# SCH_arduino_timer_mertvyak_2023-02-15.net
KiCad netlist of a schematic drawn in EasyEDA
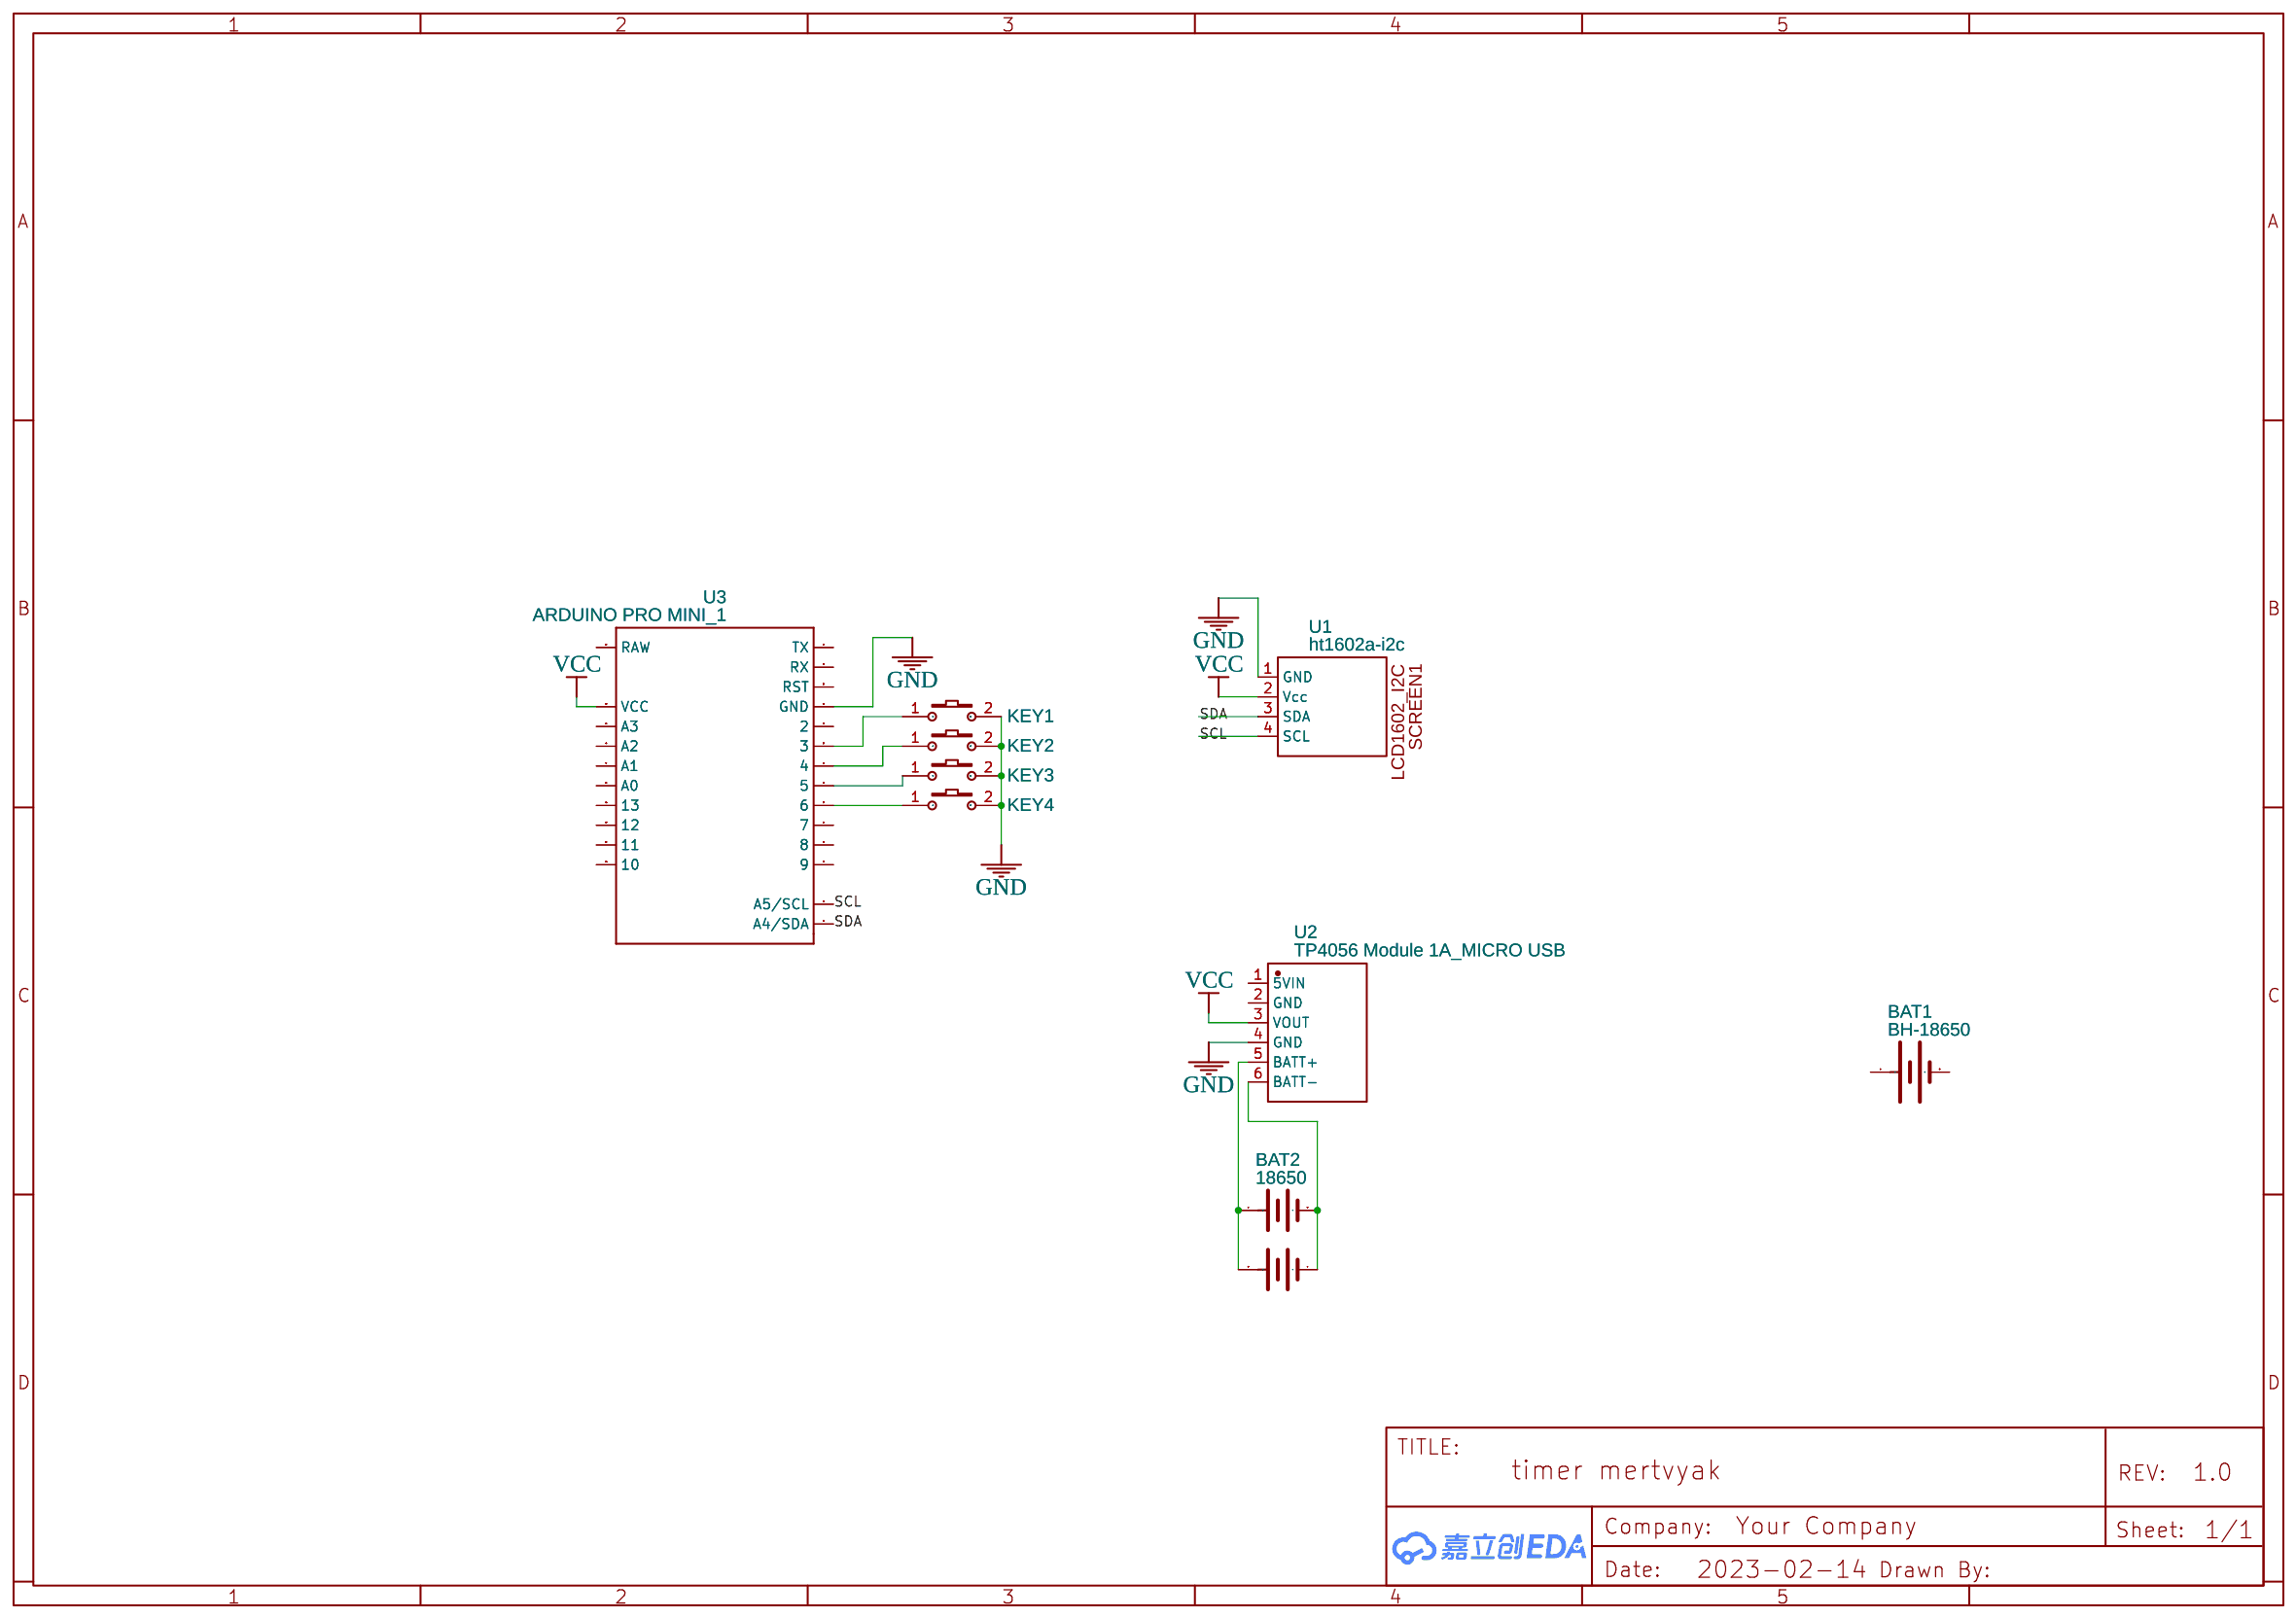
[diagram p0: schematic sheet]

(export (version "E")
  (design (tool "Eeschema 10.0.6"))
  (components
    (comp (ref "BAT1")
      (value "BH-18650")
      (fields (field (name "BOM_Supplier Part") "C9900017971"))
      (libsource (lib "") (part "BH-18650"))
    )
    (comp (ref "BAT2")
      (value "18650")
      (fields
        (field (name "BOM_Manufacturer Part") "18650并联电池盒")
        (field (name "BOM_Supplier Part") "C9900010344")
      )
      (libsource (lib "") (part "18650并联电池盒"))
    )
    (comp (ref "KEY1")
      (value "K2-3.6×6.1_SMD")
      (fields
        (field (name "BOM_Manufacturer Part") "K2-1107ST-A4SW-06")
        (field (name "BOM_Supplier Part") "C118141")
      )
      (libsource (lib "") (part "K2-3.6×6.1_SMD"))
    )
    (comp (ref "KEY2")
      (value "K2-3.6×6.1_SMD")
      (fields
        (field (name "BOM_Manufacturer Part") "K2-1107ST-A4SW-06")
        (field (name "BOM_Supplier Part") "C118141")
      )
      (libsource (lib "") (part "K2-3.6×6.1_SMD"))
    )
    (comp (ref "KEY3")
      (value "K2-3.6×6.1_SMD")
      (fields
        (field (name "BOM_Manufacturer Part") "K2-1107ST-A4SW-06")
        (field (name "BOM_Supplier Part") "C118141")
      )
      (libsource (lib "") (part "K2-3.6×6.1_SMD"))
    )
    (comp (ref "KEY4")
      (value "K2-3.6×6.1_SMD")
      (fields
        (field (name "BOM_Manufacturer Part") "K2-1107ST-A4SW-06")
        (field (name "BOM_Supplier Part") "C118141")
      )
      (libsource (lib "") (part "K2-3.6×6.1_SMD"))
    )
    (comp (ref "U1") (value "ht1602a-i2c") (libsource (lib "") (part "ht1602a-i2c")))
    (comp (ref "U2")
      (value "TP4056 Module 1A_MICRO USB")
      (fields
        (field (name "BOM_Manufacturer Part") "TP4056 MICROUSB 1A")
        (field (name "BOM_Supplier Part") "EC-1275")
      )
      (libsource (lib "") (part "TP4056 Module 1A_MICRO USB"))
    )
    (comp (ref "U3") (value "ARDUINO PRO MINI_1") (libsource (lib "") (part "ARDUINO PRO MINI_1")))
  )
  (nets
    (net (code "1") (name "/SCL") (class "Default")
      (node (ref "U1") (pin "4") (pinfunction "SCL_4") (pintype "unspecified"))
      (node (ref "U3") (pin "A5") (pinfunction "A5/SCL_A5") (pintype "unspecified"))
    )
    (net (code "2") (name "/SDA") (class "Default")
      (node (ref "U1") (pin "3") (pinfunction "SDA_3") (pintype "unspecified"))
      (node (ref "U3") (pin "A4") (pinfunction "A4/SDA_A4") (pintype "unspecified"))
    )
    (net (code "3") (name "GND") (class "Default")
      (node (ref "KEY1") (pin "2") (pinfunction "2_2") (pintype "unspecified"))
      (node (ref "KEY2") (pin "2") (pinfunction "2_2") (pintype "unspecified"))
      (node (ref "KEY3") (pin "2") (pinfunction "2_2") (pintype "unspecified"))
      (node (ref "KEY4") (pin "2") (pinfunction "2_2") (pintype "unspecified"))
      (node (ref "U1") (pin "1") (pinfunction "GND_1") (pintype "unspecified"))
      (node (ref "U2") (pin "4") (pinfunction "GND_4") (pintype "unspecified"))
      (node (ref "U3") (pin "GND") (pinfunction "GND_GND") (pintype "unspecified"))
    )
    (net (code "4") (name "Net-(U2-BATT+)") (class "Default")
      (node (ref "BAT2") (pin "1") (pinfunction "+_1") (pintype "passive"))
      (node (ref "BAT2") (pin "2") (pinfunction "+_2") (pintype "passive"))
      (node (ref "U2") (pin "5") (pinfunction "BATT+_5") (pintype "unspecified"))
    )
    (net (code "5") (name "Net-(U2-BATT-)") (class "Default")
      (node (ref "BAT2") (pin "3") (pinfunction "-_3") (pintype "passive"))
      (node (ref "BAT2") (pin "4") (pinfunction "-_4") (pintype "passive"))
      (node (ref "U2") (pin "6") (pinfunction "BATT-_6") (pintype "unspecified"))
    )
    (net (code "6") (name "Net-(U3-3)") (class "Default")
      (node (ref "KEY1") (pin "1") (pinfunction "1_1") (pintype "unspecified"))
      (node (ref "U3") (pin "D3") (pinfunction "3_D3") (pintype "unspecified"))
    )
    (net (code "7") (name "Net-(U3-4)") (class "Default")
      (node (ref "KEY2") (pin "1") (pinfunction "1_1") (pintype "unspecified"))
      (node (ref "U3") (pin "D4") (pinfunction "4_D4") (pintype "unspecified"))
    )
    (net (code "8") (name "Net-(U3-5)") (class "Default")
      (node (ref "KEY3") (pin "1") (pinfunction "1_1") (pintype "unspecified"))
      (node (ref "U3") (pin "D5") (pinfunction "5_D5") (pintype "unspecified"))
    )
    (net (code "9") (name "Net-(U3-6)") (class "Default")
      (node (ref "KEY4") (pin "1") (pinfunction "1_1") (pintype "unspecified"))
      (node (ref "U3") (pin "D6") (pinfunction "6_D6") (pintype "unspecified"))
    )
    (net (code "10") (name "VCC") (class "Default")
      (node (ref "U1") (pin "2") (pinfunction "Vcc_2") (pintype "unspecified"))
      (node (ref "U2") (pin "3") (pinfunction "VOUT_3") (pintype "unspecified"))
      (node (ref "U3") (pin "VCC") (pinfunction "VCC_VCC") (pintype "unspecified"))
    )
    (net (code "11") (name "unconnected-(BAT1-+-Pad2)") (class "Default")
      (node (ref "BAT1") (pin "2") (pinfunction "+_2") (pintype "passive"))
    )
    (net (code "12") (name "unconnected-(BAT1---Pad1)") (class "Default")
      (node (ref "BAT1") (pin "1") (pinfunction "-_1") (pintype "passive"))
    )
    (net (code "13") (name "unconnected-(U2-5VIN-Pad1)") (class "Default")
      (node (ref "U2") (pin "1") (pinfunction "5VIN_1") (pintype "unspecified"))
    )
    (net (code "14") (name "unconnected-(U2-GND-Pad2)") (class "Default")
      (node (ref "U2") (pin "2") (pinfunction "GND_2") (pintype "unspecified"))
    )
    (net (code "15") (name "unconnected-(U3-2-PadD2)") (class "Default")
      (node (ref "U3") (pin "D2") (pinfunction "2_D2") (pintype "unspecified"))
    )
    (net (code "16") (name "unconnected-(U3-7-PadD7)") (class "Default")
      (node (ref "U3") (pin "D7") (pinfunction "7_D7") (pintype "unspecified"))
    )
    (net (code "17") (name "unconnected-(U3-8-PadD8)") (class "Default")
      (node (ref "U3") (pin "D8") (pinfunction "8_D8") (pintype "unspecified"))
    )
    (net (code "18") (name "unconnected-(U3-9-PadD9)") (class "Default")
      (node (ref "U3") (pin "D9") (pinfunction "9_D9") (pintype "unspecified"))
    )
    (net (code "19") (name "unconnected-(U3-10-PadD10)") (class "Default")
      (node (ref "U3") (pin "D10") (pinfunction "10_D10") (pintype "unspecified"))
    )
    (net (code "20") (name "unconnected-(U3-11-PadD11)") (class "Default")
      (node (ref "U3") (pin "D11") (pinfunction "11_D11") (pintype "unspecified"))
    )
    (net (code "21") (name "unconnected-(U3-12-PadD12)") (class "Default")
      (node (ref "U3") (pin "D12") (pinfunction "12_D12") (pintype "unspecified"))
    )
    (net (code "22") (name "unconnected-(U3-13-PadD13)") (class "Default")
      (node (ref "U3") (pin "D13") (pinfunction "13_D13") (pintype "unspecified"))
    )
    (net (code "23") (name "unconnected-(U3-PadA0)") (class "Default")
      (node (ref "U3") (pin "A0") (pinfunction "A0_A0") (pintype "unspecified"))
    )
    (net (code "24") (name "unconnected-(U3-PadA1)") (class "Default")
      (node (ref "U3") (pin "A1") (pinfunction "A1_A1") (pintype "unspecified"))
    )
    (net (code "25") (name "unconnected-(U3-PadA2)") (class "Default")
      (node (ref "U3") (pin "A2") (pinfunction "A2_A2") (pintype "unspecified"))
    )
    (net (code "26") (name "unconnected-(U3-PadA3)") (class "Default")
      (node (ref "U3") (pin "A3") (pinfunction "A3_A3") (pintype "unspecified"))
    )
    (net (code "27") (name "unconnected-(U3-PadRAW)") (class "Default")
      (node (ref "U3") (pin "RAW") (pinfunction "RAW_RAW") (pintype "unspecified"))
    )
    (net (code "28") (name "unconnected-(U3-PadRST)") (class "Default")
      (node (ref "U3") (pin "RST") (pinfunction "RST_RST") (pintype "unspecified"))
    )
    (net (code "29") (name "unconnected-(U3-PadRX)") (class "Default")
      (node (ref "U3") (pin "RX") (pinfunction "RX_RX") (pintype "unspecified"))
    )
    (net (code "30") (name "unconnected-(U3-PadTX)") (class "Default")
      (node (ref "U3") (pin "TX") (pinfunction "TX_TX") (pintype "unspecified"))
    )
  )
)
